# T_BIAS.net
KiCad netlist of a schematic drawn in Altium Designer
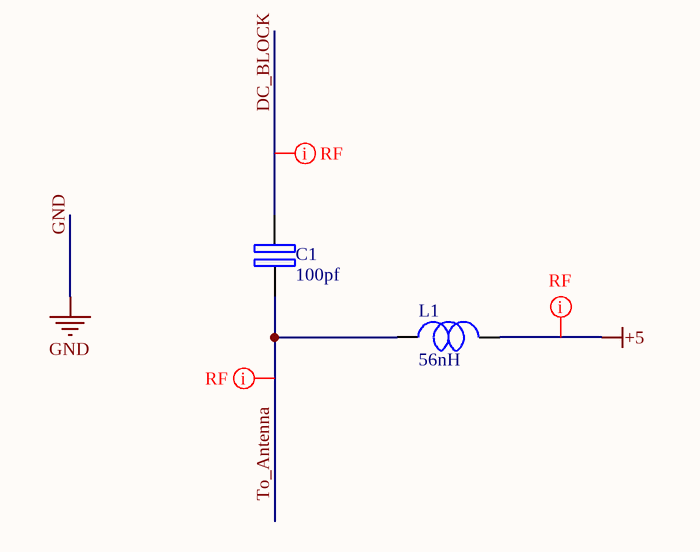
[diagram p0: T_BIAS.SchDoc]

(export (version "E")
  (design (tool "Eeschema 10.0.6"))
  (components
    (comp (ref "C1")
      (value "100pf")
      (footprint "CAPC0603X08L")
      (description "The capacitor have 2PIN in AXIAL and SMD models.\r\nall non-polar models include.")
      (fields (field (name "CREATOR") "Shahab Azmoodeh") (field (name "CREATED FOR") "HiroNegarPars"))
      (libsource (lib "HiroNegarParsMainLib") (part "Capacitor2P-NP"))
    )
    (comp (ref "L1")
      (value "56nH")
      (footprint "INDC0603X102-2L")
      (description "generic smd and dip inductors")
      (fields (field (name "CREATOR") "Milad Mohammadi Bidhandi") (field (name "CREATED FOR") "Hiro Negar"))
      (libsource (lib "HiroNegarParsMainLib") (part "Inductor2P"))
    )
  )
  (nets
    (net (code "1") (name "+5") (class "Default")
      (node (ref "L1") (pin "2") (pinfunction "2_2") (pintype "passive"))
    )
    (net (code "2") (name "/DC_BLOCK") (class "Default")
      (node (ref "C1") (pin "2") (pinfunction "2_2") (pintype "passive"))
    )
    (net (code "3") (name "/To_Antenna") (class "Default")
      (node (ref "C1") (pin "1") (pinfunction "1_1") (pintype "passive"))
      (node (ref "L1") (pin "1") (pinfunction "1_1") (pintype "passive"))
    )
  )
)
